# Kill_Switch_Fuse.net
KiCad netlist of a schematic drawn in Altium Designer
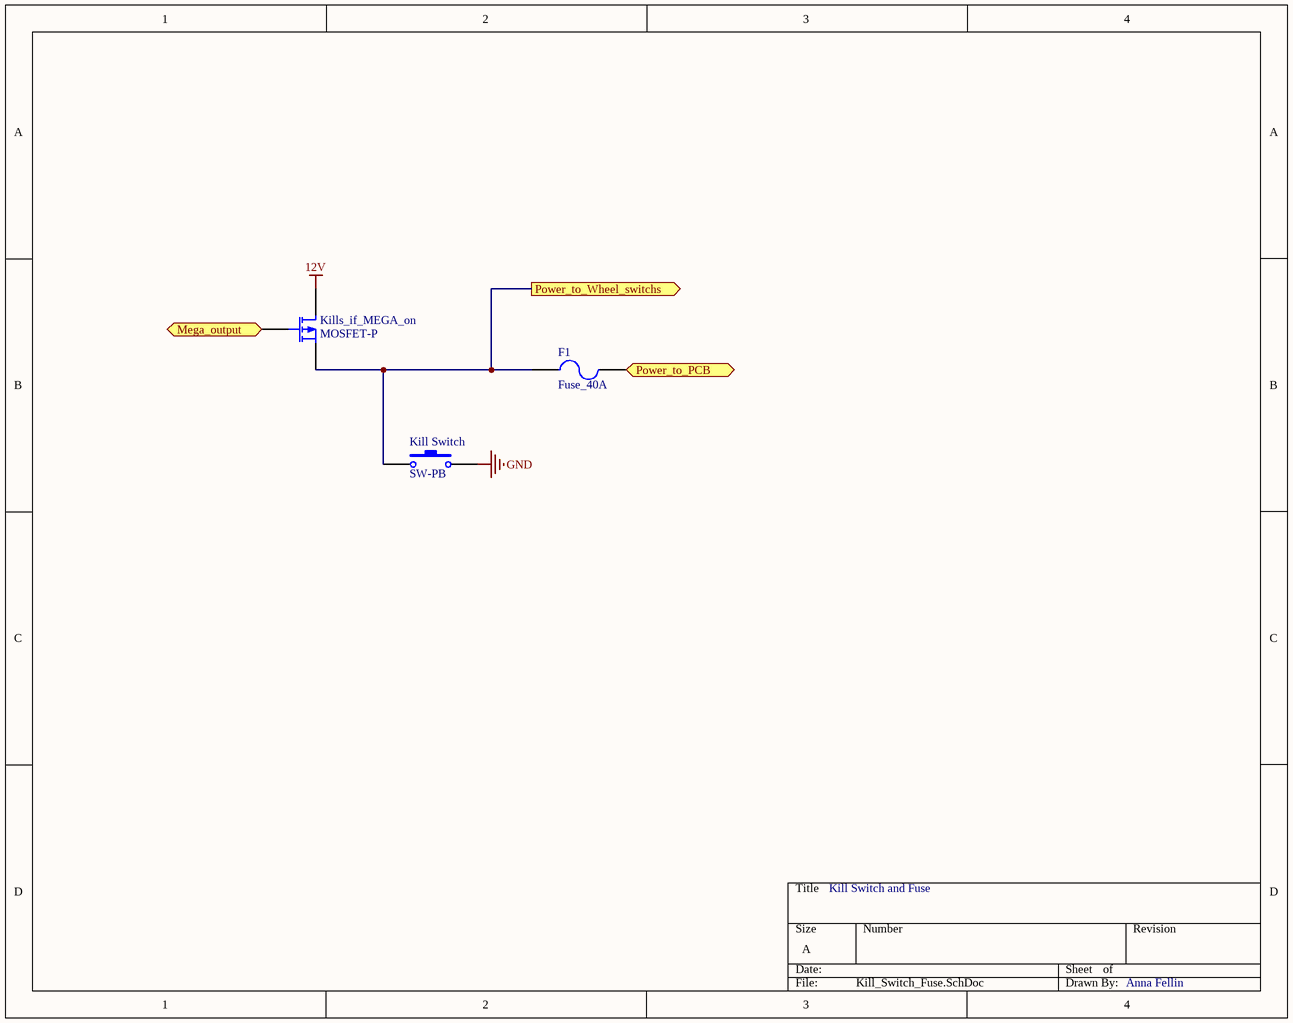
[diagram p0: Kill_Switch_Fuse.SchDoc]

(export (version "E")
  (design (tool "Eeschema 10.0.6"))
  (components
    (comp (ref "F1")
      (value "Fuse_40A")
      (footprint "PIN-W2/E2.8")
      (description "Fuse")
      (fields (field (name "PUBLISHER") "Altium Limited"))
      (libsource (lib "Miscellaneous Devices") (part "Fuse 2"))
    )
    (comp (ref "Kill Switch")
      (value "SW-PB")
      (footprint "SPST-2")
      (description "Switch")
      (fields (field (name "PUBLISHER") "Altium Limited"))
      (libsource (lib "Miscellaneous Devices") (part "SW-PB"))
    )
    (comp (ref "Kills_if_MEGA_on")
      (value "MOSFET-P")
      (footprint "E3")
      (description "P-Channel MOSFET")
      (fields (field (name "PUBLISHER") "Altium Limited"))
      (libsource (lib "Miscellaneous Devices") (part "MOSFET-P"))
    )
  )
  (nets
    (net (code "1") (name "/Mega_output") (class "Default")
      (node (ref "Kills_if_MEGA_on") (pin "2") (pinfunction "G_2") (pintype "passive"))
    )
    (net (code "2") (name "/Power_to_PCB") (class "Default")
      (node (ref "F1") (pin "2") (pinfunction "2_2") (pintype "passive"))
    )
    (net (code "3") (name "/Power_to_Wheel_switchs") (class "Default")
      (node (ref "F1") (pin "1") (pinfunction "1_1") (pintype "passive"))
      (node (ref "Kill Switch") (pin "1") (pinfunction "1_1") (pintype "passive"))
      (node (ref "Kills_if_MEGA_on") (pin "3") (pinfunction "S_3") (pintype "passive"))
    )
    (net (code "4") (name "12V") (class "Default")
      (node (ref "Kills_if_MEGA_on") (pin "1") (pinfunction "D_1") (pintype "passive"))
    )
    (net (code "5") (name "GND") (class "Default")
      (node (ref "Kill Switch") (pin "2") (pinfunction "2_2") (pintype "passive"))
    )
  )
)
